# ESP32.net
KiCad netlist of a schematic drawn in Altium Designer
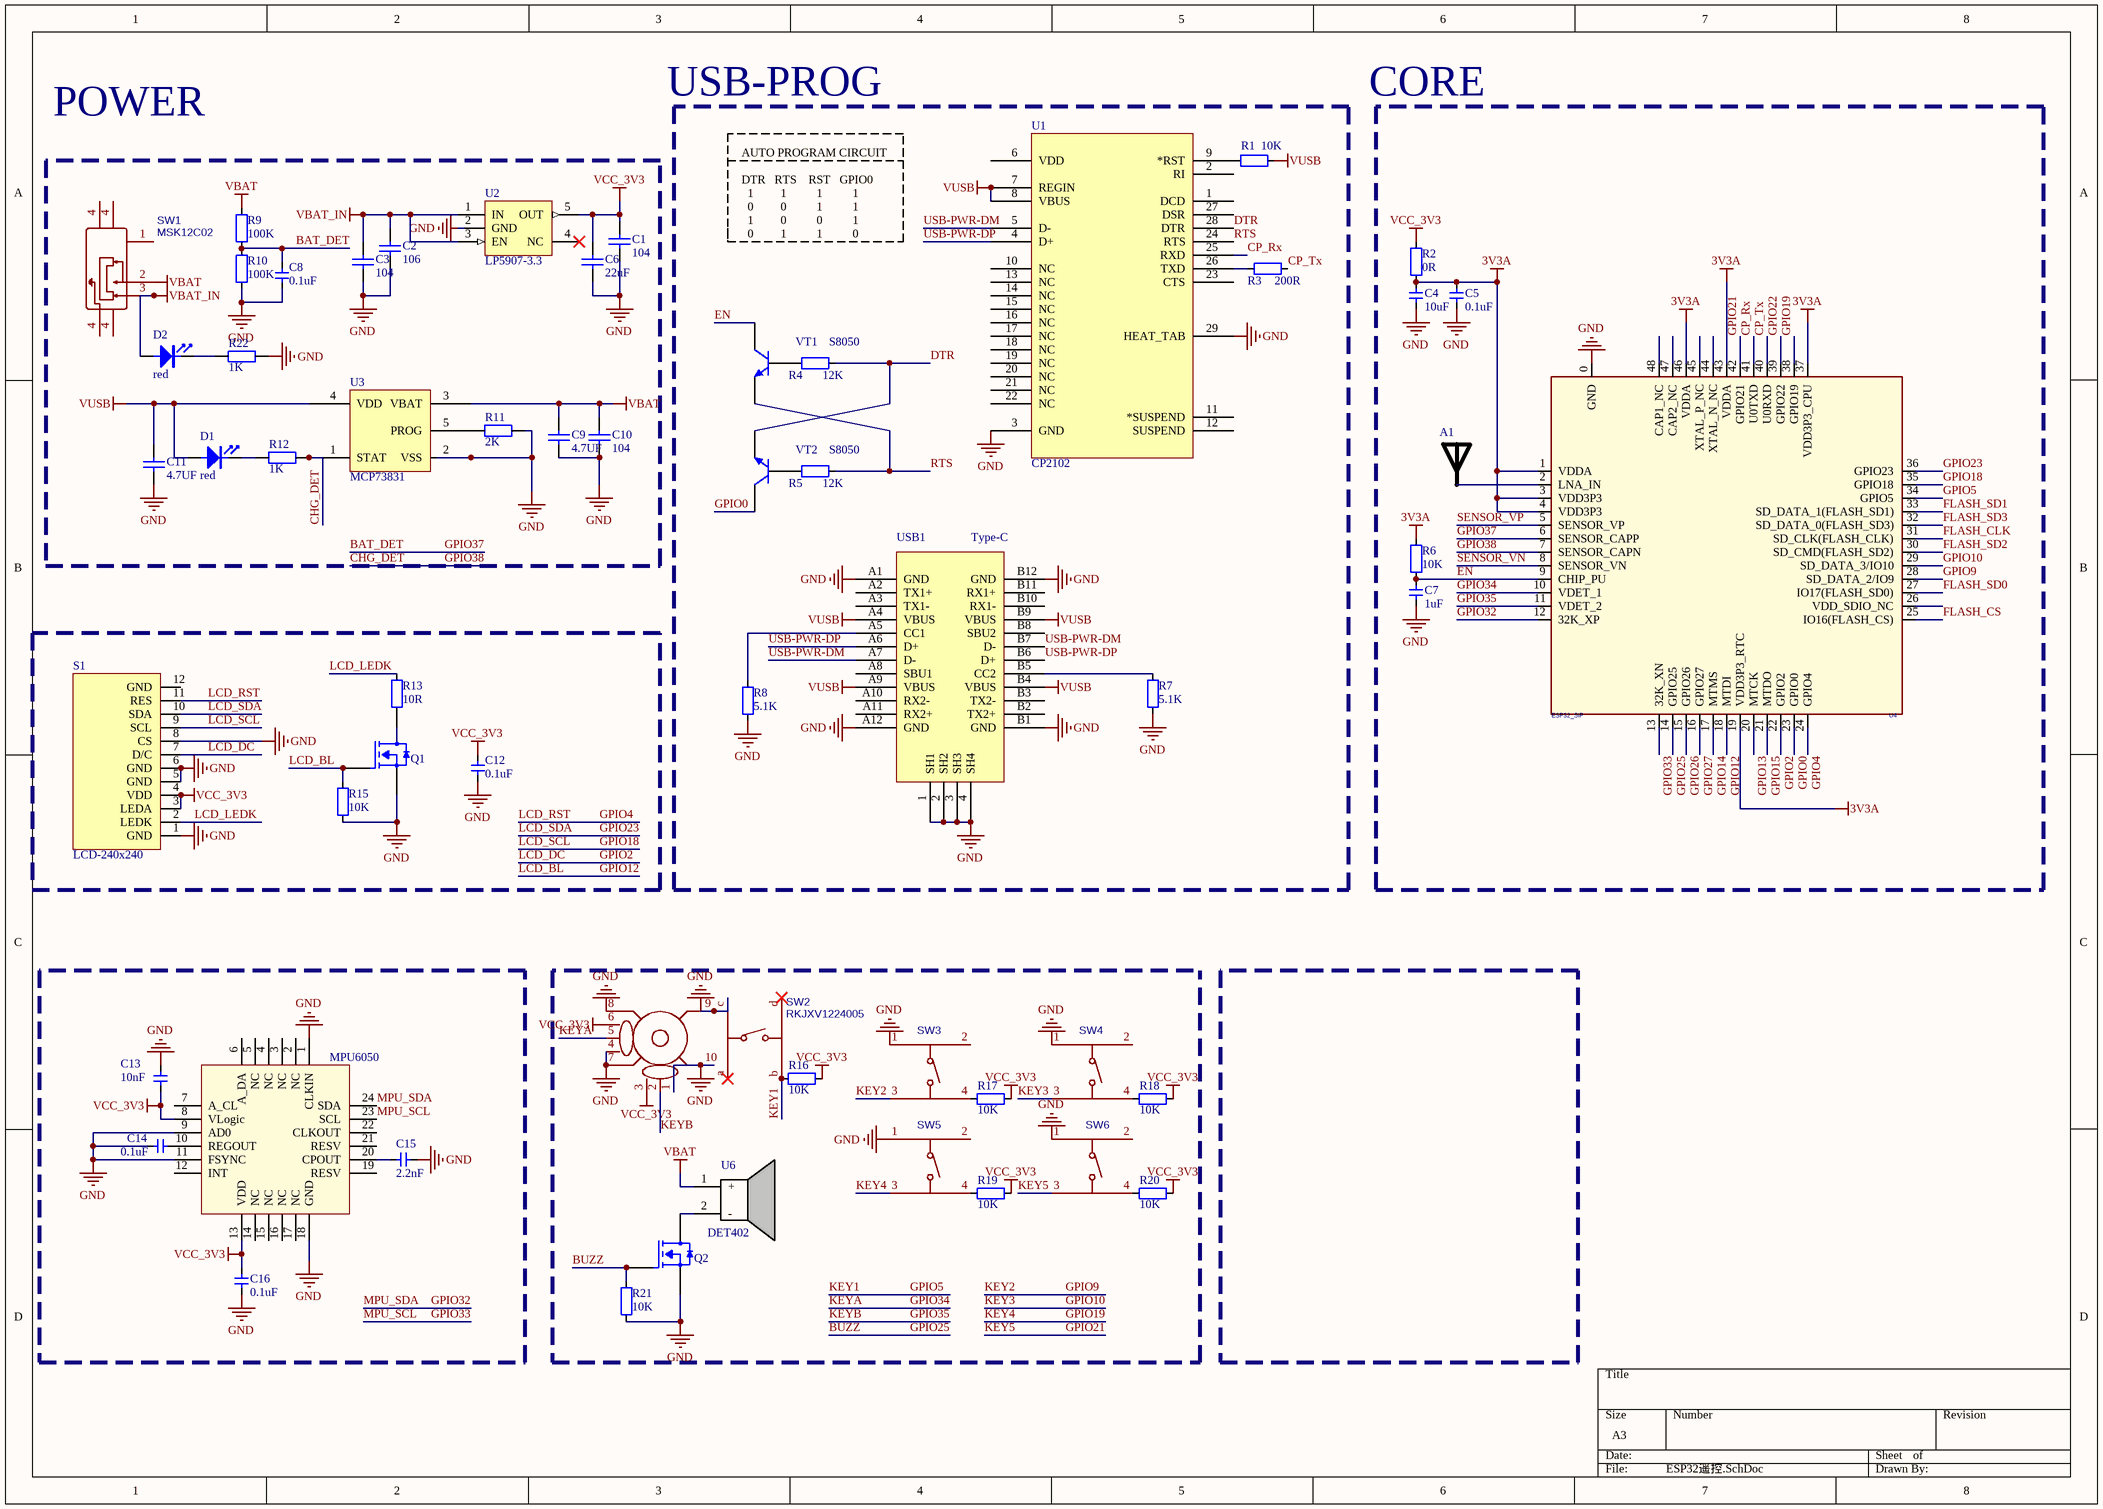
[diagram p0: ESP32遥控.SchDoc]

(export (version "E")
  (design (tool "Eeschema 10.0.6"))
  (components
    (comp (ref "A1")
      (value "RAINSUN")
      (footprint "ANT-Rainsun-AN5120")
      (libsource (lib "MyPcbLib") (part "ANT-Rainsun-AP5120"))
    )
    (comp (ref "C1")
      (value "104")
      (footprint "CAP_0402")
      (fields (field (name "C") "104"))
      (libsource (lib "元件库") (part "cap"))
    )
    (comp (ref "C2")
      (value "106")
      (footprint "电容_C0603")
      (fields (field (name "C") "106"))
      (libsource (lib "元件库") (part "cap"))
    )
    (comp (ref "C3")
      (value "104")
      (footprint "CAP_0402")
      (fields (field (name "C") "104"))
      (libsource (lib "元件库") (part "cap"))
    )
    (comp (ref "C4")
      (value "10uF")
      (footprint "CAP_0402")
      (description "Capacitor")
      (libsource (lib "MyPcbLib") (part "电容-0402"))
    )
    (comp (ref "C5")
      (value "0.1uF")
      (footprint "CAP_0402")
      (description "Capacitor")
      (libsource (lib "MyPcbLib") (part "电容-0402"))
    )
    (comp (ref "C6")
      (value "22uF")
      (footprint "电容_C1206")
      (fields (field (name "C") "22uF"))
      (libsource (lib "元件库") (part "cap"))
    )
    (comp (ref "C7")
      (value "1uF")
      (footprint "CAP_0402")
      (description "Capacitor")
      (libsource (lib "MyPcbLib") (part "电容-0402"))
    )
    (comp (ref "C8")
      (value "0.1uF")
      (footprint "CAP_0402")
      (description "Capacitor")
      (libsource (lib "MyPcbLib") (part "电容-0402"))
    )
    (comp (ref "C9")
      (value "4.7UF")
      (footprint "电容_C0805")
      (fields (field (name "C") "4.7UF"))
      (libsource (lib "元件库") (part "cap"))
    )
    (comp (ref "C10")
      (value "104")
      (footprint "CAP_0402")
      (fields (field (name "C") "104"))
      (libsource (lib "元件库") (part "cap"))
    )
    (comp (ref "C11")
      (value "4.7UF")
      (footprint "电容_C0805")
      (fields (field (name "C") "4.7UF"))
      (libsource (lib "元件库") (part "cap"))
    )
    (comp (ref "C12")
      (value "0.1uF")
      (footprint "CAP_0402")
      (description "Capacitor")
      (libsource (lib "MyPcbLib") (part "电容-0402"))
    )
    (comp (ref "C13")
      (value "10nF")
      (footprint "CAP_0402")
      (description "Capacitor")
      (libsource (lib "MyPcbLib") (part "电容-0402"))
    )
    (comp (ref "C14")
      (value "0.1uF")
      (footprint "CAP_0402")
      (description "Capacitor")
      (libsource (lib "MyPcbLib") (part "电容-0402"))
    )
    (comp (ref "C15")
      (value "2.2nF")
      (footprint "CAP_0402")
      (description "Capacitor")
      (libsource (lib "MyPcbLib") (part "电容-0402"))
    )
    (comp (ref "C16")
      (value "0.1uF")
      (footprint "CAP_0402")
      (description "Capacitor")
      (libsource (lib "MyPcbLib") (part "电容-0402"))
    )
    (comp (ref "D1") (value "red") (footprint "LED_0603") (libsource (lib "元件库") (part "LED")))
    (comp (ref "D2") (value "red") (footprint "LED_0603") (libsource (lib "元件库") (part "LED")))
    (comp (ref "Q1")
      (value "AO3400A")
      (footprint "SOT23-3")
      (description "N-MOS")
      (libsource (lib "MyPcbLib") (part "AO3400A"))
    )
    (comp (ref "Q2")
      (value "AO3400A")
      (footprint "SOT23-3")
      (description "N-MOS")
      (libsource (lib "MyPcbLib") (part "AO3400A"))
    )
    (comp (ref "R1")
      (value "10K")
      (footprint "RES_0402")
      (description "Resistor")
      (libsource (lib "MyPcbLib") (part "电阻-0402"))
    )
    (comp (ref "R2")
      (value "0R")
      (footprint "RES_0402")
      (description "Resistor")
      (libsource (lib "") (part "电阻-0402_2"))
    )
    (comp (ref "R3")
      (value "200R")
      (footprint "RES_0402")
      (description "Resistor")
      (libsource (lib "MyPcbLib") (part "电阻-0402"))
    )
    (comp (ref "R4")
      (value "12K")
      (footprint "RES_0402")
      (description "Resistor")
      (libsource (lib "MyPcbLib") (part "电阻-0402"))
    )
    (comp (ref "R5")
      (value "12K")
      (footprint "RES_0402")
      (description "Resistor")
      (libsource (lib "MyPcbLib") (part "电阻-0402"))
    )
    (comp (ref "R6")
      (value "10K")
      (footprint "RES_0402")
      (description "Resistor")
      (libsource (lib "") (part "电阻-0402_2"))
    )
    (comp (ref "R7")
      (value "5.1K")
      (footprint "RES_0402")
      (description "Resistor")
      (libsource (lib "") (part "电阻-0402_2"))
    )
    (comp (ref "R8")
      (value "5.1K")
      (footprint "RES_0402")
      (description "Resistor")
      (libsource (lib "") (part "电阻-0402_2"))
    )
    (comp (ref "R9")
      (value "100K")
      (footprint "RES_0402")
      (description "Resistor")
      (libsource (lib "") (part "电阻-0402_3"))
    )
    (comp (ref "R10")
      (value "100K")
      (footprint "RES_0402")
      (description "Resistor")
      (libsource (lib "") (part "电阻-0402_3"))
    )
    (comp (ref "R11")
      (value "2K")
      (footprint "RES_0402")
      (fields (field (name "R") "2K"))
      (libsource (lib "元件库") (part "Res"))
    )
    (comp (ref "R12")
      (value "1K")
      (footprint "RES_0402")
      (fields (field (name "R") "1K"))
      (libsource (lib "元件库") (part "Res"))
    )
    (comp (ref "R13")
      (value "10R")
      (footprint "RES_0402")
      (description "Resistor")
      (libsource (lib "") (part "电阻-0402_3"))
    )
    (comp (ref "R15")
      (value "10K")
      (footprint "RES_0402")
      (description "Resistor")
      (libsource (lib "") (part "电阻-0402_3"))
    )
    (comp (ref "R16")
      (value "10K")
      (footprint "RES_0402")
      (description "Resistor")
      (libsource (lib "") (part "电阻-0402_1"))
    )
    (comp (ref "R17")
      (value "10K")
      (footprint "RES_0402")
      (description "Resistor")
      (libsource (lib "MyPcbLib") (part "电阻-0402"))
    )
    (comp (ref "R18")
      (value "10K")
      (footprint "RES_0402")
      (description "Resistor")
      (libsource (lib "MyPcbLib") (part "电阻-0402"))
    )
    (comp (ref "R19")
      (value "10K")
      (footprint "RES_0402")
      (description "Resistor")
      (libsource (lib "MyPcbLib") (part "电阻-0402"))
    )
    (comp (ref "R20")
      (value "10K")
      (footprint "RES_0402")
      (description "Resistor")
      (libsource (lib "MyPcbLib") (part "电阻-0402"))
    )
    (comp (ref "R21")
      (value "10K")
      (footprint "RES_0402")
      (description "Resistor")
      (libsource (lib "") (part "电阻-0402_3"))
    )
    (comp (ref "R22")
      (value "1K")
      (footprint "RES_0402")
      (fields (field (name "R") "1K"))
      (libsource (lib "元件库") (part "Res"))
    )
    (comp (ref "S1")
      (value "LCD-240x240")
      (footprint "LCD-240x240-FlUSH-154")
      (description "显示屏")
      (libsource (lib "mLib") (part "LCD-240x240"))
    )
    (comp (ref "SW1")
      (value "MSK12C02")
      (footprint "SW-TH_MSK12C02")
      (fields (field (name "BOM_SUPPLIER PART") "C431540") (field (name "CONTRIBUTOR") "LCSC"))
      (libsource (lib "88DianZhen") (part "MSK12C02"))
    )
    (comp (ref "SW2")
      (value "RKJXV1224005")
      (footprint "SW-TH_RKJXV1224005")
      (fields (field (name "BOM_SUPPLIER PART") "C146170") (field (name "CONTRIBUTOR") "LCSC"))
      (libsource (lib "altium-import") (part "root_1_RKJXV1224005_"))
    )
    (comp (ref "SW3")
      (value "~")
      (footprint "KEY-SMD_4P-L6.0-W6.0-P4.50-LS8.6")
      (fields
        (field (name "BOM_SUPPLIER PART") "C782843")
        (field (name "BOM_MANUFACTURER PART") "TS-1095S-A16B2-C2D1")
        (field (name "CONTRIBUTOR") "LCSC")
      )
      (libsource (lib "altium-import") (part "root_0_TS-1095S-A16B2-C2D1_"))
    )
    (comp (ref "SW4")
      (value "~")
      (footprint "KEY-SMD_4P-L6.0-W6.0-P4.50-LS8.6")
      (fields
        (field (name "BOM_SUPPLIER PART") "C782843")
        (field (name "BOM_MANUFACTURER PART") "TS-1095S-A16B2-C2D1")
        (field (name "CONTRIBUTOR") "LCSC")
      )
      (libsource (lib "altium-import") (part "root_0_TS-1095S-A16B2-C2D1_"))
    )
    (comp (ref "SW5")
      (value "~")
      (footprint "KEY-SMD_4P-L6.0-W6.0-P4.50-LS8.6")
      (fields
        (field (name "BOM_SUPPLIER PART") "C782843")
        (field (name "BOM_MANUFACTURER PART") "TS-1095S-A16B2-C2D1")
        (field (name "CONTRIBUTOR") "LCSC")
      )
      (libsource (lib "altium-import") (part "root_0_TS-1095S-A16B2-C2D1_"))
    )
    (comp (ref "SW6")
      (value "~")
      (footprint "KEY-SMD_4P-L6.0-W6.0-P4.50-LS8.6")
      (fields
        (field (name "BOM_SUPPLIER PART") "C782843")
        (field (name "BOM_MANUFACTURER PART") "TS-1095S-A16B2-C2D1")
        (field (name "CONTRIBUTOR") "LCSC")
      )
      (libsource (lib "altium-import") (part "root_0_TS-1095S-A16B2-C2D1_"))
    )
    (comp (ref "U1")
      (value "CP2102")
      (footprint "QFN-28")
      (description "USB转TTL")
      (libsource (lib "mLib") (part "CP2102"))
    )
    (comp (ref "U2")
      (value "LP5907-3.3")
      (footprint "SOT23-5")
      (description "LDO")
      (libsource (lib "WatchX_TEST") (part "LP5907"))
    )
    (comp (ref "U3")
      (value "MCP73831")
      (footprint "SOT23-5")
      (description "线性充电管理控制器")
      (libsource (lib "TriggersLib") (part "MCP73831"))
    )
    (comp (ref "U4")
      (value "ESP32_SIP")
      (footprint "QFN-48_7X7")
      (libsource (lib "MyPcbLib") (part "ESP32-PICO"))
    )
    (comp (ref "U5")
      (value "MPU6050")
      (footprint "QFN-24")
      (description "六轴传感器")
      (libsource (lib "mLib") (part "MPU6050"))
    )
    (comp (ref "U6") (value "DET402") (footprint "DET402") (libsource (lib "MyPcbLib") (part "DET402")))
    (comp (ref "USB1")
      (value "Type-C")
      (footprint "Type-C-TOP")
      (libsource (lib "MyPcbLib") (part "USB-Type-C-TOP"))
    )
    (comp (ref "VT1")
      (value "S8050")
      (footprint "SMT_TRIODE_NPN")
      (description "Surface mount NPN transistor, package SOT-23")
      (libsource (lib "MyPcbLib") (part "SMT_TRIODE_NPN"))
    )
    (comp (ref "VT2")
      (value "S8050")
      (footprint "SMT_TRIODE_NPN")
      (description "Surface mount NPN transistor, package SOT-23")
      (libsource (lib "MyPcbLib") (part "SMT_TRIODE_NPN"))
    )
  )
  (nets
    (net (code "1") (name "/BAT_DET") (class "Default")
      (node (ref "C8") (pin "2") (pinfunction "2_2") (pintype "passive"))
      (node (ref "R10") (pin "2") (pinfunction "2_2") (pintype "passive"))
      (node (ref "R9") (pin "1") (pinfunction "1_1") (pintype "passive"))
      (node (ref "U4") (pin "6") (pinfunction "SENSOR_CAPP_6") (pintype "passive"))
    )
    (net (code "2") (name "/BUZZ") (class "Default")
      (node (ref "Q2") (pin "1") (pinfunction "G_1") (pintype "passive"))
      (node (ref "R21") (pin "2") (pinfunction "2_2") (pintype "passive"))
      (node (ref "U4") (pin "14") (pinfunction "GPIO25_14") (pintype "passive"))
    )
    (net (code "3") (name "/CHG_DET") (class "Default")
      (node (ref "R12") (pin "1") (pinfunction "1_1") (pintype "passive"))
      (node (ref "U3") (pin "1") (pinfunction "STAT_1") (pintype "passive"))
      (node (ref "U4") (pin "7") (pinfunction "SENSOR_CAPN_7") (pintype "passive"))
    )
    (net (code "4") (name "/CP_Rx") (class "Default")
      (node (ref "U1") (pin "25") (pinfunction "RXD_25") (pintype "passive"))
      (node (ref "U4") (pin "41") (pinfunction "U0TXD_41") (pintype "power_in"))
    )
    (net (code "5") (name "/CP_Tx") (class "Default")
      (node (ref "R3") (pin "1") (pinfunction "1_1") (pintype "passive"))
      (node (ref "U4") (pin "40") (pinfunction "U0RXD_40") (pintype "power_in"))
    )
    (net (code "6") (name "/DTR") (class "Default")
      (node (ref "R4") (pin "1") (pinfunction "1_1") (pintype "passive"))
      (node (ref "U1") (pin "28") (pinfunction "DTR_28") (pintype "passive"))
      (node (ref "VT2") (pin "2") (pinfunction "E_2") (pintype "passive"))
    )
    (net (code "7") (name "/EN") (class "Default")
      (node (ref "C7") (pin "1") (pinfunction "1_1") (pintype "passive"))
      (node (ref "R6") (pin "2") (pinfunction "2_2") (pintype "passive"))
      (node (ref "U4") (pin "9") (pinfunction "CHIP_PU_9") (pintype "passive"))
      (node (ref "VT1") (pin "3") (pinfunction "C_3") (pintype "passive"))
    )
    (net (code "8") (name "/FLASH_CLK") (class "Default")
      (node (ref "U4") (pin "31") (pinfunction "SD_CLK(FLASH_CLK)_31") (pintype "passive"))
    )
    (net (code "9") (name "/FLASH_CS") (class "Default")
      (node (ref "U4") (pin "25") (pinfunction "IO16(FLASH_CS)_25") (pintype "passive"))
    )
    (net (code "10") (name "/FLASH_SD0") (class "Default")
      (node (ref "U4") (pin "27") (pinfunction "IO17(FLASH_SD0)_27") (pintype "passive"))
    )
    (net (code "11") (name "/FLASH_SD1") (class "Default")
      (node (ref "U4") (pin "33") (pinfunction "SD_DATA_1(FLASH_SD1)_33") (pintype "passive"))
    )
    (net (code "12") (name "/FLASH_SD2") (class "Default")
      (node (ref "U4") (pin "30") (pinfunction "SD_CMD(FLASH_SD2)_30") (pintype "passive"))
    )
    (net (code "13") (name "/FLASH_SD3") (class "Default")
      (node (ref "U4") (pin "32") (pinfunction "SD_DATA_0(FLASH_SD3)_32") (pintype "passive"))
    )
    (net (code "14") (name "/GPIO0") (class "Default")
      (node (ref "U4") (pin "23") (pinfunction "GPIO0_23") (pintype "passive"))
      (node (ref "VT2") (pin "3") (pinfunction "C_3") (pintype "passive"))
    )
    (net (code "15") (name "/GPIO2") (class "Default")
      (node (ref "S1") (pin "7") (pinfunction "D/C_7") (pintype "passive"))
      (node (ref "U4") (pin "22") (pinfunction "GPIO2_22") (pintype "passive"))
    )
    (net (code "16") (name "/GPIO4") (class "Default")
      (node (ref "S1") (pin "11") (pinfunction "RES_11") (pintype "passive"))
      (node (ref "U4") (pin "24") (pinfunction "GPIO4_24") (pintype "passive"))
    )
    (net (code "17") (name "/GPIO5") (class "Default")
      (node (ref "R16") (pin "1") (pinfunction "1_1") (pintype "passive"))
      (node (ref "SW2") (pin "b") (pinfunction "b_b") (pintype "passive"))
      (node (ref "U4") (pin "34") (pinfunction "GPIO5_34") (pintype "passive"))
    )
    (net (code "18") (name "/GPIO9") (class "Default")
      (node (ref "SW3") (pin "3") (pinfunction "3_3") (pintype "passive"))
      (node (ref "U4") (pin "28") (pinfunction "SD_DATA_2/IO9_28") (pintype "passive"))
    )
    (net (code "19") (name "/GPIO10") (class "Default")
      (node (ref "SW4") (pin "3") (pinfunction "3_3") (pintype "passive"))
      (node (ref "U4") (pin "29") (pinfunction "SD_DATA_3/IO10_29") (pintype "passive"))
    )
    (net (code "20") (name "/GPIO12") (class "Default")
      (node (ref "Q1") (pin "1") (pinfunction "G_1") (pintype "passive"))
      (node (ref "R15") (pin "2") (pinfunction "2_2") (pintype "passive"))
      (node (ref "U4") (pin "18") (pinfunction "MTDI_18") (pintype "passive"))
    )
    (net (code "21") (name "/GPIO13") (class "Default")
      (node (ref "U4") (pin "20") (pinfunction "MTCK_20") (pintype "passive"))
    )
    (net (code "22") (name "/GPIO14") (class "Default")
      (node (ref "U4") (pin "17") (pinfunction "MTMS_17") (pintype "passive"))
    )
    (net (code "23") (name "/GPIO15") (class "Default")
      (node (ref "U4") (pin "21") (pinfunction "MTDO_21") (pintype "passive"))
    )
    (net (code "24") (name "/GPIO18") (class "Default")
      (node (ref "S1") (pin "9") (pinfunction "SCL_9") (pintype "passive"))
      (node (ref "U4") (pin "35") (pinfunction "GPIO18_35") (pintype "passive"))
    )
    (net (code "25") (name "/GPIO19") (class "Default")
      (node (ref "SW5") (pin "3") (pinfunction "3_3") (pintype "passive"))
      (node (ref "U4") (pin "38") (pinfunction "GPIO19_38") (pintype "passive"))
    )
    (net (code "26") (name "/GPIO21") (class "Default")
      (node (ref "SW6") (pin "3") (pinfunction "3_3") (pintype "passive"))
      (node (ref "U4") (pin "42") (pinfunction "GPIO21_42") (pintype "passive"))
    )
    (net (code "27") (name "/GPIO22") (class "Default")
      (node (ref "U4") (pin "39") (pinfunction "GPIO22_39") (pintype "passive"))
    )
    (net (code "28") (name "/GPIO23") (class "Default")
      (node (ref "S1") (pin "10") (pinfunction "SDA_10") (pintype "passive"))
      (node (ref "U4") (pin "36") (pinfunction "GPIO23_36") (pintype "passive"))
    )
    (net (code "29") (name "/GPIO26") (class "Default")
      (node (ref "U4") (pin "15") (pinfunction "GPIO26_15") (pintype "passive"))
    )
    (net (code "30") (name "/GPIO27") (class "Default")
      (node (ref "U4") (pin "16") (pinfunction "GPIO27_16") (pintype "passive"))
    )
    (net (code "31") (name "/GPIO32") (class "Default")
      (node (ref "U4") (pin "12") (pinfunction "32K_XP_12") (pintype "passive"))
      (node (ref "U5") (pin "24") (pinfunction "SDA_24") (pintype "passive"))
    )
    (net (code "32") (name "/GPIO33") (class "Default")
      (node (ref "U4") (pin "13") (pinfunction "32K_XN_13") (pintype "passive"))
      (node (ref "U5") (pin "23") (pinfunction "SCL_23") (pintype "passive"))
    )
    (net (code "33") (name "/GPIO34") (class "Default")
      (node (ref "SW2") (pin "5") (pinfunction "DTA_5") (pintype "passive"))
      (node (ref "U4") (pin "10") (pinfunction "VDET_1_10") (pintype "passive"))
    )
    (net (code "34") (name "/GPIO35") (class "Default")
      (node (ref "SW2") (pin "2") (pinfunction "DTA_2") (pintype "passive"))
      (node (ref "U4") (pin "11") (pinfunction "VDET_2_11") (pintype "passive"))
    )
    (net (code "35") (name "/LCD_LEDK") (class "Default")
      (node (ref "R13") (pin "2") (pinfunction "2_2") (pintype "passive"))
      (node (ref "S1") (pin "2") (pinfunction "LEDK_2") (pintype "passive"))
    )
    (net (code "36") (name "/RTS") (class "Default")
      (node (ref "R5") (pin "1") (pinfunction "1_1") (pintype "passive"))
      (node (ref "U1") (pin "24") (pinfunction "RTS_24") (pintype "passive"))
      (node (ref "VT1") (pin "2") (pinfunction "E_2") (pintype "passive"))
    )
    (net (code "37") (name "/SENSOR_VN") (class "Default")
      (node (ref "U4") (pin "8") (pinfunction "SENSOR_VN_8") (pintype "passive"))
    )
    (net (code "38") (name "/SENSOR_VP") (class "Default")
      (node (ref "U4") (pin "5") (pinfunction "SENSOR_VP_5") (pintype "passive"))
    )
    (net (code "39") (name "/USB-PWR-DM") (class "Default")
      (node (ref "U1") (pin "5") (pinfunction "D-_5") (pintype "passive"))
      (node (ref "USB1") (pin "A7") (pinfunction "D-_A7") (pintype "passive"))
      (node (ref "USB1") (pin "B7") (pinfunction "D-_B7") (pintype "passive"))
    )
    (net (code "40") (name "/USB-PWR-DP") (class "Default")
      (node (ref "U1") (pin "4") (pinfunction "D+_4") (pintype "passive"))
      (node (ref "USB1") (pin "A6") (pinfunction "D+_A6") (pintype "passive"))
      (node (ref "USB1") (pin "B6") (pinfunction "D+_B6") (pintype "passive"))
    )
    (net (code "41") (name "3V3A") (class "Default")
      (node (ref "C4") (pin "2") (pinfunction "2_2") (pintype "passive"))
      (node (ref "C5") (pin "2") (pinfunction "2_2") (pintype "passive"))
      (node (ref "R2") (pin "2") (pinfunction "2_2") (pintype "passive"))
      (node (ref "R6") (pin "1") (pinfunction "1_1") (pintype "passive"))
      (node (ref "U4") (pin "1") (pinfunction "VDDA_1") (pintype "power_in"))
      (node (ref "U4") (pin "19") (pinfunction "VDD3P3_RTC_19") (pintype "power_in"))
      (node (ref "U4") (pin "3") (pinfunction "VDD3P3_3") (pintype "power_in"))
      (node (ref "U4") (pin "37") (pinfunction "VDD3P3_CPU_37") (pintype "power_in"))
      (node (ref "U4") (pin "4") (pinfunction "VDD3P3_4") (pintype "power_in"))
      (node (ref "U4") (pin "43") (pinfunction "VDDA_43") (pintype "power_in"))
      (node (ref "U4") (pin "46") (pinfunction "VDDA_46") (pintype "power_in"))
    )
    (net (code "42") (name "GND") (class "Default")
      (node (ref "C1") (pin "1") (pinfunction "1_1") (pintype "passive"))
      (node (ref "C10") (pin "2") (pinfunction "2_2") (pintype "passive"))
      (node (ref "C11") (pin "1") (pinfunction "1_1") (pintype "passive"))
      (node (ref "C12") (pin "1") (pinfunction "1_1") (pintype "passive"))
      (node (ref "C13") (pin "2") (pinfunction "2_2") (pintype "passive"))
      (node (ref "C14") (pin "2") (pinfunction "2_2") (pintype "passive"))
      (node (ref "C15") (pin "1") (pinfunction "1_1") (pintype "passive"))
      (node (ref "C16") (pin "1") (pinfunction "1_1") (pintype "passive"))
      (node (ref "C2") (pin "1") (pinfunction "1_1") (pintype "passive"))
      (node (ref "C3") (pin "1") (pinfunction "1_1") (pintype "passive"))
      (node (ref "C4") (pin "1") (pinfunction "1_1") (pintype "passive"))
      (node (ref "C5") (pin "1") (pinfunction "1_1") (pintype "passive"))
      (node (ref "C6") (pin "1") (pinfunction "1_1") (pintype "passive"))
      (node (ref "C7") (pin "2") (pinfunction "2_2") (pintype "passive"))
      (node (ref "C8") (pin "1") (pinfunction "1_1") (pintype "passive"))
      (node (ref "C9") (pin "1") (pinfunction "1_1") (pintype "passive"))
      (node (ref "Q1") (pin "2") (pinfunction "S_2") (pintype "passive"))
      (node (ref "Q2") (pin "2") (pinfunction "S_2") (pintype "passive"))
      (node (ref "R10") (pin "1") (pinfunction "1_1") (pintype "passive"))
      (node (ref "R11") (pin "1") (pinfunction "1_1") (pintype "passive"))
      (node (ref "R15") (pin "1") (pinfunction "1_1") (pintype "passive"))
      (node (ref "R21") (pin "1") (pinfunction "1_1") (pintype "passive"))
      (node (ref "R22") (pin "1") (pinfunction "1_1") (pintype "passive"))
      (node (ref "R7") (pin "2") (pinfunction "2_2") (pintype "passive"))
      (node (ref "R8") (pin "2") (pinfunction "2_2") (pintype "passive"))
      (node (ref "S1") (pin "1") (pinfunction "GND_1") (pintype "passive"))
      (node (ref "S1") (pin "5") (pinfunction "GND_5") (pintype "passive"))
      (node (ref "S1") (pin "6") (pinfunction "GND_6") (pintype "passive"))
      (node (ref "S1") (pin "8") (pinfunction "CS_8") (pintype "passive"))
      (node (ref "SW2") (pin "1") (pinfunction "B_1") (pintype "passive"))
      (node (ref "SW2") (pin "10") (pinfunction "GND_10") (pintype "passive"))
      (node (ref "SW2") (pin "4") (pinfunction "A_4") (pintype "passive"))
      (node (ref "SW2") (pin "7") (pinfunction "GND_7") (pintype "passive"))
      (node (ref "SW2") (pin "8") (pinfunction "GND_8") (pintype "passive"))
      (node (ref "SW2") (pin "9") (pinfunction "GND_9") (pintype "passive"))
      (node (ref "SW2") (pin "c") (pinfunction "c_c") (pintype "passive"))
      (node (ref "SW3") (pin "1") (pinfunction "1_1") (pintype "passive"))
      (node (ref "SW4") (pin "1") (pinfunction "1_1") (pintype "passive"))
      (node (ref "SW5") (pin "1") (pinfunction "1_1") (pintype "passive"))
      (node (ref "SW6") (pin "1") (pinfunction "1_1") (pintype "passive"))
      (node (ref "U1") (pin "29") (pinfunction "HEAT_TAB_29") (pintype "passive"))
      (node (ref "U1") (pin "3") (pinfunction "GND_3") (pintype "passive"))
      (node (ref "U2") (pin "2") (pinfunction "GND_2") (pintype "passive"))
      (node (ref "U3") (pin "2") (pinfunction "VSS_2") (pintype "passive"))
      (node (ref "U4") (pin "0") (pinfunction "GND_0") (pintype "power_in"))
      (node (ref "U5") (pin "1") (pinfunction "CLKIN_1") (pintype "passive"))
      (node (ref "U5") (pin "11") (pinfunction "FSYNC_11") (pintype "passive"))
      (node (ref "U5") (pin "18") (pinfunction "GND_18") (pintype "passive"))
      (node (ref "U5") (pin "9") (pinfunction "AD0_9") (pintype "passive"))
      (node (ref "USB1") (pin "1") (pinfunction "SH1_1") (pintype "passive"))
      (node (ref "USB1") (pin "2") (pinfunction "SH2_2") (pintype "passive"))
      (node (ref "USB1") (pin "3") (pinfunction "SH3_3") (pintype "passive"))
      (node (ref "USB1") (pin "4") (pinfunction "SH4_4") (pintype "passive"))
      (node (ref "USB1") (pin "A1") (pinfunction "GND_A1") (pintype "passive"))
      (node (ref "USB1") (pin "A12") (pinfunction "GND_A12") (pintype "passive"))
      (node (ref "USB1") (pin "B1") (pinfunction "GND_B1") (pintype "passive"))
      (node (ref "USB1") (pin "B12") (pinfunction "GND_B12") (pintype "passive"))
    )
    (net (code "43") (name "Net-(D1-PadK)") (class "Default")
      (node (ref "D1") (pin "K") (pinfunction "K_K") (pintype "passive"))
      (node (ref "R12") (pin "2") (pinfunction "2_2") (pintype "passive"))
    )
    (net (code "44") (name "Net-(D2-PadK)") (class "Default")
      (node (ref "D2") (pin "K") (pinfunction "K_K") (pintype "passive"))
      (node (ref "R22") (pin "2") (pinfunction "2_2") (pintype "passive"))
    )
    (net (code "45") (name "Net-(Q1-D)") (class "Default")
      (node (ref "Q1") (pin "3") (pinfunction "D_3") (pintype "passive"))
      (node (ref "R13") (pin "1") (pinfunction "1_1") (pintype "passive"))
    )
    (net (code "46") (name "Net-(Q2-D)") (class "Default")
      (node (ref "Q2") (pin "3") (pinfunction "D_3") (pintype "passive"))
      (node (ref "U6") (pin "2") (pinfunction "-_2") (pintype "passive"))
    )
    (net (code "47") (name "Net-(R17-Pad2)") (class "Default")
      (node (ref "R17") (pin "2") (pinfunction "2_2") (pintype "passive"))
      (node (ref "SW3") (pin "4") (pinfunction "4_4") (pintype "passive"))
    )
    (net (code "48") (name "Net-(R18-Pad2)") (class "Default")
      (node (ref "R18") (pin "2") (pinfunction "2_2") (pintype "passive"))
      (node (ref "SW4") (pin "4") (pinfunction "4_4") (pintype "passive"))
    )
    (net (code "49") (name "Net-(R19-Pad2)") (class "Default")
      (node (ref "R19") (pin "2") (pinfunction "2_2") (pintype "passive"))
      (node (ref "SW5") (pin "4") (pinfunction "4_4") (pintype "passive"))
    )
    (net (code "50") (name "Net-(R20-Pad2)") (class "Default")
      (node (ref "R20") (pin "2") (pinfunction "2_2") (pintype "passive"))
      (node (ref "SW6") (pin "4") (pinfunction "4_4") (pintype "passive"))
    )
    (net (code "51") (name "Net-(U1-*RST)") (class "Default")
      (node (ref "R1") (pin "2") (pinfunction "2_2") (pintype "passive"))
      (node (ref "U1") (pin "9") (pinfunction "*RST_9") (pintype "passive"))
    )
    (net (code "52") (name "Net-(U1-TXD)") (class "Default")
      (node (ref "R3") (pin "2") (pinfunction "2_2") (pintype "passive"))
      (node (ref "U1") (pin "26") (pinfunction "TXD_26") (pintype "passive"))
    )
    (net (code "53") (name "Net-(U3-PROG)") (class "Default")
      (node (ref "R11") (pin "2") (pinfunction "2_2") (pintype "passive"))
      (node (ref "U3") (pin "5") (pinfunction "PROG_5") (pintype "passive"))
    )
    (net (code "54") (name "Net-(U4-LNA_IN)") (class "Default")
      (node (ref "A1") (pin "1") (pinfunction "1_1") (pintype "passive"))
      (node (ref "U4") (pin "2") (pinfunction "LNA_IN_2") (pintype "passive"))
    )
    (net (code "55") (name "Net-(U5-CPOUT)") (class "Default")
      (node (ref "C15") (pin "2") (pinfunction "2_2") (pintype "passive"))
      (node (ref "U5") (pin "20") (pinfunction "CPOUT_20") (pintype "passive"))
    )
    (net (code "56") (name "Net-(U5-REGOUT)") (class "Default")
      (node (ref "C14") (pin "1") (pinfunction "1_1") (pintype "passive"))
      (node (ref "U5") (pin "10") (pinfunction "REGOUT_10") (pintype "passive"))
    )
    (net (code "57") (name "Net-(USB1-CC1)") (class "Default")
      (node (ref "R8") (pin "1") (pinfunction "1_1") (pintype "passive"))
      (node (ref "USB1") (pin "A5") (pinfunction "CC1_A5") (pintype "passive"))
    )
    (net (code "58") (name "Net-(USB1-CC2)") (class "Default")
      (node (ref "R7") (pin "1") (pinfunction "1_1") (pintype "passive"))
      (node (ref "USB1") (pin "B5") (pinfunction "CC2_B5") (pintype "passive"))
    )
    (net (code "59") (name "Net-(VT1-B)") (class "Default")
      (node (ref "R4") (pin "2") (pinfunction "2_2") (pintype "passive"))
      (node (ref "VT1") (pin "1") (pinfunction "B_1") (pintype "passive"))
    )
    (net (code "60") (name "Net-(VT2-B)") (class "Default")
      (node (ref "R5") (pin "2") (pinfunction "2_2") (pintype "passive"))
      (node (ref "VT2") (pin "1") (pinfunction "B_1") (pintype "passive"))
    )
    (net (code "61") (name "VBAT") (class "Default")
      (node (ref "C10") (pin "1") (pinfunction "1_1") (pintype "passive"))
      (node (ref "C9") (pin "2") (pinfunction "2_2") (pintype "passive"))
      (node (ref "R9") (pin "2") (pinfunction "2_2") (pintype "passive"))
      (node (ref "SW1") (pin "2") (pinfunction "2_2") (pintype "passive"))
      (node (ref "U3") (pin "3") (pinfunction "VBAT_3") (pintype "passive"))
      (node (ref "U6") (pin "1") (pinfunction "+_1") (pintype "passive"))
    )
    (net (code "62") (name "VBAT_IN") (class "Default")
      (node (ref "C2") (pin "2") (pinfunction "2_2") (pintype "passive"))
      (node (ref "C3") (pin "2") (pinfunction "2_2") (pintype "passive"))
      (node (ref "D2") (pin "A") (pinfunction "A_A") (pintype "passive"))
      (node (ref "SW1") (pin "3") (pinfunction "3_3") (pintype "passive"))
      (node (ref "U2") (pin "1") (pinfunction "IN_1") (pintype "power_in"))
      (node (ref "U2") (pin "3") (pinfunction "EN_3") (pintype "input"))
    )
    (net (code "63") (name "VCC_3V3") (class "Default")
      (node (ref "C1") (pin "2") (pinfunction "2_2") (pintype "passive"))
      (node (ref "C12") (pin "2") (pinfunction "2_2") (pintype "passive"))
      (node (ref "C13") (pin "1") (pinfunction "1_1") (pintype "passive"))
      (node (ref "C16") (pin "2") (pinfunction "2_2") (pintype "passive"))
      (node (ref "C6") (pin "2") (pinfunction "2_2") (pintype "passive"))
      (node (ref "R16") (pin "2") (pinfunction "2_2") (pintype "passive"))
      (node (ref "R17") (pin "1") (pinfunction "1_1") (pintype "passive"))
      (node (ref "R18") (pin "1") (pinfunction "1_1") (pintype "passive"))
      (node (ref "R19") (pin "1") (pinfunction "1_1") (pintype "passive"))
      (node (ref "R2") (pin "1") (pinfunction "1_1") (pintype "passive"))
      (node (ref "R20") (pin "1") (pinfunction "1_1") (pintype "passive"))
      (node (ref "S1") (pin "3") (pinfunction "LEDA_3") (pintype "passive"))
      (node (ref "S1") (pin "4") (pinfunction "VDD_4") (pintype "passive"))
      (node (ref "SW2") (pin "3") (pinfunction "A_3") (pintype "passive"))
      (node (ref "SW2") (pin "6") (pinfunction "B_6") (pintype "passive"))
      (node (ref "U2") (pin "5") (pinfunction "OUT_5") (pintype "output"))
      (node (ref "U5") (pin "13") (pinfunction "VDD_13") (pintype "passive"))
      (node (ref "U5") (pin "8") (pinfunction "VLogic_8") (pintype "passive"))
    )
    (net (code "64") (name "VUSB") (class "Default")
      (node (ref "C11") (pin "2") (pinfunction "2_2") (pintype "passive"))
      (node (ref "D1") (pin "A") (pinfunction "A_A") (pintype "passive"))
      (node (ref "R1") (pin "1") (pinfunction "1_1") (pintype "passive"))
      (node (ref "U1") (pin "7") (pinfunction "REGIN_7") (pintype "passive"))
      (node (ref "U1") (pin "8") (pinfunction "VBUS_8") (pintype "passive"))
      (node (ref "U3") (pin "4") (pinfunction "VDD_4") (pintype "passive"))
      (node (ref "USB1") (pin "A4") (pinfunction "VBUS_A4") (pintype "passive"))
      (node (ref "USB1") (pin "A9") (pinfunction "VBUS_A9") (pintype "passive"))
      (node (ref "USB1") (pin "B4") (pinfunction "VBUS_B4") (pintype "passive"))
      (node (ref "USB1") (pin "B9") (pinfunction "VBUS_B9") (pintype "passive"))
    )
    (net (code "65") (name "unconnected-(S1-GND-Pad12)") (class "Default")
      (node (ref "S1") (pin "12") (pinfunction "GND_12") (pintype "passive"))
    )
    (net (code "66") (name "unconnected-(SW1-Pad1)") (class "Default")
      (node (ref "SW1") (pin "1") (pinfunction "1_1") (pintype "passive"))
    )
    (net (code "67") (name "unconnected-(SW1-Pad4)") (class "Default")
      (node (ref "SW1") (pin "4") (pinfunction "4_4") (pintype "passive"))
    )
    (net (code "68") (name "unconnected-(SW1-Pad4)_1") (class "Default")
      (node (ref "SW1") (pin "4") (pinfunction "4_4") (pintype "passive"))
    )
    (net (code "69") (name "unconnected-(SW1-Pad4)_2") (class "Default")
      (node (ref "SW1") (pin "4") (pinfunction "4_4") (pintype "passive"))
    )
    (net (code "70") (name "unconnected-(SW1-Pad4)_3") (class "Default")
      (node (ref "SW1") (pin "4") (pinfunction "4_4") (pintype "passive"))
    )
    (net (code "71") (name "unconnected-(SW2-Pada)") (class "Default")
      (node (ref "SW2") (pin "a") (pinfunction "a_a") (pintype "passive+no_connect"))
    )
    (net (code "72") (name "unconnected-(SW2-Padd)") (class "Default")
      (node (ref "SW2") (pin "d") (pinfunction "d_d") (pintype "passive+no_connect"))
    )
    (net (code "73") (name "unconnected-(SW3-Pad2)") (class "Default")
      (node (ref "SW3") (pin "2") (pinfunction "2_2") (pintype "passive"))
    )
    (net (code "74") (name "unconnected-(SW4-Pad2)") (class "Default")
      (node (ref "SW4") (pin "2") (pinfunction "2_2") (pintype "passive"))
    )
    (net (code "75") (name "unconnected-(SW5-Pad2)") (class "Default")
      (node (ref "SW5") (pin "2") (pinfunction "2_2") (pintype "passive"))
    )
    (net (code "76") (name "unconnected-(SW6-Pad2)") (class "Default")
      (node (ref "SW6") (pin "2") (pinfunction "2_2") (pintype "passive"))
    )
    (net (code "77") (name "unconnected-(U1-*SUSPEND-Pad11)") (class "Default")
      (node (ref "U1") (pin "11") (pinfunction "*SUSPEND_11") (pintype "passive"))
    )
    (net (code "78") (name "unconnected-(U1-CTS-Pad23)") (class "Default")
      (node (ref "U1") (pin "23") (pinfunction "CTS_23") (pintype "passive"))
    )
    (net (code "79") (name "unconnected-(U1-DCD-Pad1)") (class "Default")
      (node (ref "U1") (pin "1") (pinfunction "DCD_1") (pintype "passive"))
    )
    (net (code "80") (name "unconnected-(U1-DSR-Pad27)") (class "Default")
      (node (ref "U1") (pin "27") (pinfunction "DSR_27") (pintype "passive"))
    )
    (net (code "81") (name "unconnected-(U1-NC-Pad10)") (class "Default")
      (node (ref "U1") (pin "10") (pinfunction "NC_10") (pintype "passive"))
    )
    (net (code "82") (name "unconnected-(U1-NC-Pad13)") (class "Default")
      (node (ref "U1") (pin "13") (pinfunction "NC_13") (pintype "passive"))
    )
    (net (code "83") (name "unconnected-(U1-NC-Pad14)") (class "Default")
      (node (ref "U1") (pin "14") (pinfunction "NC_14") (pintype "passive"))
    )
    (net (code "84") (name "unconnected-(U1-NC-Pad15)") (class "Default")
      (node (ref "U1") (pin "15") (pinfunction "NC_15") (pintype "passive"))
    )
    (net (code "85") (name "unconnected-(U1-NC-Pad16)") (class "Default")
      (node (ref "U1") (pin "16") (pinfunction "NC_16") (pintype "passive"))
    )
    (net (code "86") (name "unconnected-(U1-NC-Pad17)") (class "Default")
      (node (ref "U1") (pin "17") (pinfunction "NC_17") (pintype "passive"))
    )
    (net (code "87") (name "unconnected-(U1-NC-Pad18)") (class "Default")
      (node (ref "U1") (pin "18") (pinfunction "NC_18") (pintype "passive"))
    )
    (net (code "88") (name "unconnected-(U1-NC-Pad19)") (class "Default")
      (node (ref "U1") (pin "19") (pinfunction "NC_19") (pintype "passive"))
    )
    (net (code "89") (name "unconnected-(U1-NC-Pad20)") (class "Default")
      (node (ref "U1") (pin "20") (pinfunction "NC_20") (pintype "passive"))
    )
    (net (code "90") (name "unconnected-(U1-NC-Pad21)") (class "Default")
      (node (ref "U1") (pin "21") (pinfunction "NC_21") (pintype "passive"))
    )
    (net (code "91") (name "unconnected-(U1-NC-Pad22)") (class "Default")
      (node (ref "U1") (pin "22") (pinfunction "NC_22") (pintype "passive"))
    )
    (net (code "92") (name "unconnected-(U1-RI-Pad2)") (class "Default")
      (node (ref "U1") (pin "2") (pinfunction "RI_2") (pintype "passive"))
    )
    (net (code "93") (name "unconnected-(U1-SUSPEND-Pad12)") (class "Default")
      (node (ref "U1") (pin "12") (pinfunction "SUSPEND_12") (pintype "passive"))
    )
    (net (code "94") (name "unconnected-(U1-VDD-Pad6)") (class "Default")
      (node (ref "U1") (pin "6") (pinfunction "VDD_6") (pintype "passive"))
    )
    (net (code "95") (name "unconnected-(U2-NC-Pad4)") (class "Default")
      (node (ref "U2") (pin "4") (pinfunction "NC_4") (pintype "passive+no_connect"))
    )
    (net (code "96") (name "unconnected-(U4-CAP1_NC-Pad48)") (class "Default")
      (node (ref "U4") (pin "48") (pinfunction "CAP1_NC_48") (pintype "passive"))
    )
    (net (code "97") (name "unconnected-(U4-CAP2_NC-Pad47)") (class "Default")
      (node (ref "U4") (pin "47") (pinfunction "CAP2_NC_47") (pintype "passive"))
    )
    (net (code "98") (name "unconnected-(U4-VDD_SDIO_NC-Pad26)") (class "Default")
      (node (ref "U4") (pin "26") (pinfunction "VDD_SDIO_NC_26") (pintype "passive"))
    )
    (net (code "99") (name "unconnected-(U4-XTAL_N_NC-Pad44)") (class "Default")
      (node (ref "U4") (pin "44") (pinfunction "XTAL_N_NC_44") (pintype "passive"))
    )
    (net (code "100") (name "unconnected-(U4-XTAL_P_NC-Pad45)") (class "Default")
      (node (ref "U4") (pin "45") (pinfunction "XTAL_P_NC_45") (pintype "passive"))
    )
    (net (code "101") (name "unconnected-(U5-A_CL-Pad7)") (class "Default")
      (node (ref "U5") (pin "7") (pinfunction "A_CL_7") (pintype "passive"))
    )
    (net (code "102") (name "unconnected-(U5-A_DA-Pad6)") (class "Default")
      (node (ref "U5") (pin "6") (pinfunction "A_DA_6") (pintype "passive"))
    )
    (net (code "103") (name "unconnected-(U5-CLKOUT-Pad22)") (class "Default")
      (node (ref "U5") (pin "22") (pinfunction "CLKOUT_22") (pintype "passive"))
    )
    (net (code "104") (name "unconnected-(U5-INT-Pad12)") (class "Default")
      (node (ref "U5") (pin "12") (pinfunction "INT_12") (pintype "passive"))
    )
    (net (code "105") (name "unconnected-(U5-NC-Pad2)") (class "Default")
      (node (ref "U5") (pin "2") (pinfunction "NC_2") (pintype "passive"))
    )
    (net (code "106") (name "unconnected-(U5-NC-Pad3)") (class "Default")
      (node (ref "U5") (pin "3") (pinfunction "NC_3") (pintype "passive"))
    )
    (net (code "107") (name "unconnected-(U5-NC-Pad4)") (class "Default")
      (node (ref "U5") (pin "4") (pinfunction "NC_4") (pintype "passive"))
    )
    (net (code "108") (name "unconnected-(U5-NC-Pad5)") (class "Default")
      (node (ref "U5") (pin "5") (pinfunction "NC_5") (pintype "passive"))
    )
    (net (code "109") (name "unconnected-(U5-NC-Pad14)") (class "Default")
      (node (ref "U5") (pin "14") (pinfunction "NC_14") (pintype "passive"))
    )
    (net (code "110") (name "unconnected-(U5-NC-Pad15)") (class "Default")
      (node (ref "U5") (pin "15") (pinfunction "NC_15") (pintype "passive"))
    )
    (net (code "111") (name "unconnected-(U5-NC-Pad16)") (class "Default")
      (node (ref "U5") (pin "16") (pinfunction "NC_16") (pintype "passive"))
    )
    (net (code "112") (name "unconnected-(U5-NC-Pad17)") (class "Default")
      (node (ref "U5") (pin "17") (pinfunction "NC_17") (pintype "passive"))
    )
    (net (code "113") (name "unconnected-(U5-RESV-Pad19)") (class "Default")
      (node (ref "U5") (pin "19") (pinfunction "RESV_19") (pintype "passive"))
    )
    (net (code "114") (name "unconnected-(U5-RESV-Pad21)") (class "Default")
      (node (ref "U5") (pin "21") (pinfunction "RESV_21") (pintype "passive"))
    )
    (net (code "115") (name "unconnected-(USB1-RX1+-PadB11)") (class "Default")
      (node (ref "USB1") (pin "B11") (pinfunction "RX1+_B11") (pintype "passive"))
    )
    (net (code "116") (name "unconnected-(USB1-RX1--PadB10)") (class "Default")
      (node (ref "USB1") (pin "B10") (pinfunction "RX1-_B10") (pintype "passive"))
    )
    (net (code "117") (name "unconnected-(USB1-RX2+-PadA11)") (class "Default")
      (node (ref "USB1") (pin "A11") (pinfunction "RX2+_A11") (pintype "passive"))
    )
    (net (code "118") (name "unconnected-(USB1-RX2--PadA10)") (class "Default")
      (node (ref "USB1") (pin "A10") (pinfunction "RX2-_A10") (pintype "passive"))
    )
    (net (code "119") (name "unconnected-(USB1-SBU1-PadA8)") (class "Default")
      (node (ref "USB1") (pin "A8") (pinfunction "SBU1_A8") (pintype "passive"))
    )
    (net (code "120") (name "unconnected-(USB1-SBU2-PadB8)") (class "Default")
      (node (ref "USB1") (pin "B8") (pinfunction "SBU2_B8") (pintype "passive"))
    )
    (net (code "121") (name "unconnected-(USB1-TX1+-PadA2)") (class "Default")
      (node (ref "USB1") (pin "A2") (pinfunction "TX1+_A2") (pintype "passive"))
    )
    (net (code "122") (name "unconnected-(USB1-TX1--PadA3)") (class "Default")
      (node (ref "USB1") (pin "A3") (pinfunction "TX1-_A3") (pintype "passive"))
    )
    (net (code "123") (name "unconnected-(USB1-TX2+-PadB2)") (class "Default")
      (node (ref "USB1") (pin "B2") (pinfunction "TX2+_B2") (pintype "passive"))
    )
    (net (code "124") (name "unconnected-(USB1-TX2--PadB3)") (class "Default")
      (node (ref "USB1") (pin "B3") (pinfunction "TX2-_B3") (pintype "passive"))
    )
  )
)
